# sensie.net
KiCad netlist of a schematic drawn in EAGLE
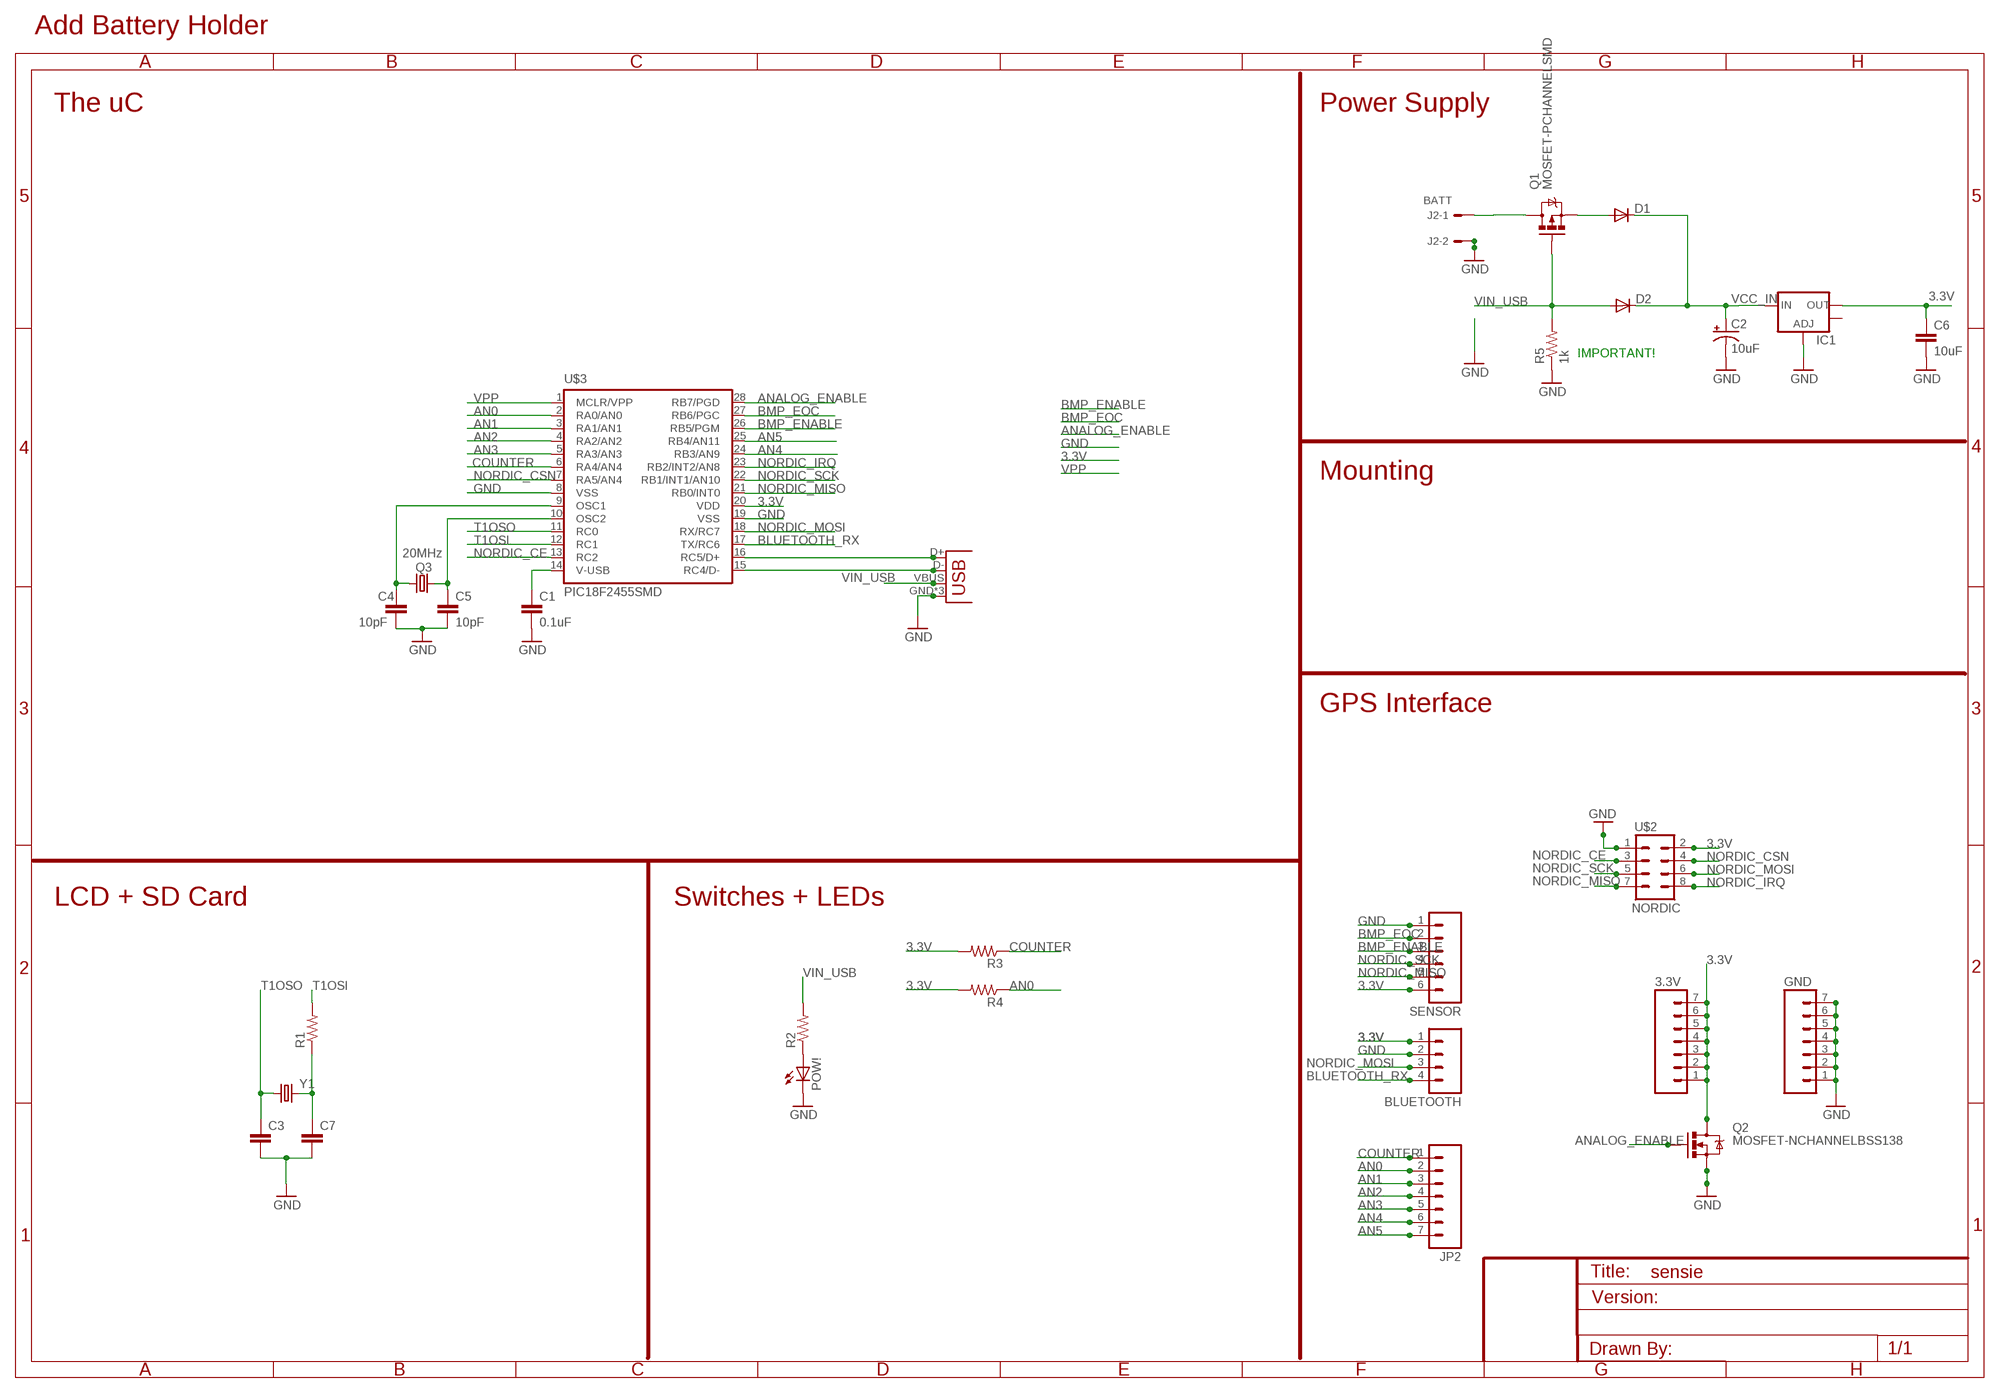
[diagram p0: schematic, sheet 1]

(export (version "E")
  (design (tool "Eeschema 10.0.6"))
  (components
    (comp (ref "3.3V")
      (value "M07")
      (footprint "eagle-import:1X07")
      (libsource (lib "eagle-import") (part "M07"))
    )
    (comp (ref "BLUETOOTH")
      (value "M04PTH")
      (footprint "eagle-import:1X04")
      (libsource (lib "eagle-import") (part "M04PTH"))
    )
    (comp (ref "C1")
      (value "0.1uF")
      (footprint "eagle-import:0805")
      (libsource (lib "eagle-import") (part "CAP0805"))
    )
    (comp (ref "C2")
      (value "10uF")
      (footprint "eagle-import:EIA3528")
      (libsource (lib "eagle-import") (part "CAP_POL3528"))
    )
    (comp (ref "C3")
      (value "CAP0603-CAP")
      (footprint "eagle-import:0603-CAP")
      (libsource (lib "eagle-import") (part "SparkFun-Passives_CAP0603-CAP"))
    )
    (comp (ref "C4")
      (value "10pF")
      (footprint "eagle-import:0805")
      (libsource (lib "eagle-import") (part "CAP0805"))
    )
    (comp (ref "C5")
      (value "10pF")
      (footprint "eagle-import:0805")
      (libsource (lib "eagle-import") (part "CAP0805"))
    )
    (comp (ref "C6")
      (value "10uF")
      (footprint "eagle-import:GRM43D")
      (libsource (lib "eagle-import") (part "CAPSMD"))
    )
    (comp (ref "C7")
      (value "CAP0603-CAP")
      (footprint "eagle-import:0603-CAP")
      (libsource (lib "eagle-import") (part "SparkFun-Passives_CAP0603-CAP"))
    )
    (comp (ref "D1")
      (value "DIODESOD")
      (footprint "eagle-import:SOD-323")
      (libsource (lib "eagle-import") (part "DIODESOD"))
    )
    (comp (ref "D2")
      (value "DIODESOD")
      (footprint "eagle-import:SOD-323")
      (libsource (lib "eagle-import") (part "DIODESOD"))
    )
    (comp (ref "GND")
      (value "M07")
      (footprint "eagle-import:1X07")
      (libsource (lib "eagle-import") (part "M07"))
    )
    (comp (ref "IC1")
      (value "V_REG_LM1117SOT223")
      (footprint "eagle-import:SOT223")
      (libsource (lib "eagle-import") (part "V_REG_LM1117SOT223"))
    )
    (comp (ref "J2")
      (value "BATT")
      (footprint "eagle-import:B2B-PH-K-S")
      (libsource (lib "eagle-import") (part "JST-PH-2-BS"))
    )
    (comp (ref "JP2")
      (value "M07")
      (footprint "eagle-import:1X07")
      (libsource (lib "eagle-import") (part "M07"))
    )
    (comp (ref "JP3")
      (value "USB-MICROB")
      (footprint "eagle-import:USB-MICROB")
      (libsource (lib "eagle-import") (part "USB-MICROB"))
    )
    (comp (ref "POW!")
      (value "LED0603")
      (footprint "eagle-import:LED-0603")
      (libsource (lib "eagle-import") (part "LED0603"))
    )
    (comp (ref "Q1")
      (value "MOSFET-PCHANNELSMD")
      (footprint "eagle-import:SOT23-3")
      (libsource (lib "eagle-import") (part "MOSFET-PCHANNELSMD"))
    )
    (comp (ref "Q2")
      (value "MOSFET-NCHANNELBSS138")
      (footprint "eagle-import:SOT23")
      (libsource (lib "eagle-import") (part "MOSFET-NCHANNELBSS138"))
    )
    (comp (ref "Q3")
      (value "20MHz")
      (footprint "eagle-import:HC49UP")
      (libsource (lib "eagle-import") (part "CRYSTALSMD"))
    )
    (comp (ref "R1")
      (value "RESISTOR0603-RES")
      (footprint "eagle-import:0603-RES")
      (libsource (lib "eagle-import") (part "SparkFun-Passives_RESISTOR0603-RES"))
    )
    (comp (ref "R2")
      (value "RESISTOR0603-RES")
      (footprint "eagle-import:0603-RES")
      (libsource (lib "eagle-import") (part "SparkFun-Passives_RESISTOR0603-RES"))
    )
    (comp (ref "R3")
      (value "RESISTOR0603-RES")
      (footprint "eagle-import:0603-RES")
      (libsource (lib "eagle-import") (part "SparkFun-Passives_RESISTOR0603-RES"))
    )
    (comp (ref "R4")
      (value "RESISTOR0603-RES")
      (footprint "eagle-import:0603-RES")
      (libsource (lib "eagle-import") (part "SparkFun-Passives_RESISTOR0603-RES"))
    )
    (comp (ref "R5")
      (value "1k")
      (footprint "eagle-import:0805")
      (libsource (lib "eagle-import") (part "RESISTOR"))
    )
    (comp (ref "SENSOR")
      (value "M06SIP")
      (footprint "eagle-import:1X06")
      (libsource (lib "eagle-import") (part "M06SIP"))
    )
    (comp (ref "U$2")
      (value "NORDIC")
      (footprint "eagle-import:2X4")
      (libsource (lib "eagle-import") (part "M04X2"))
    )
    (comp (ref "U$3")
      (value "PIC18F2455SMD")
      (footprint "eagle-import:SO-28W")
      (libsource (lib "eagle-import") (part "PIC18F2455SMD"))
    )
    (comp (ref "Y1")
      (value "CRYSTAL32-SMD")
      (footprint "eagle-import:CRYSTAL-32KHZ-SMD")
      (libsource (lib "eagle-import") (part "SparkFun-FreqCtrl_CRYSTAL32-SMD"))
    )
  )
  (nets
    (net (code "1") (name "/3.3V") (class "Default")
      (node (ref "3.3V") (pin "1") (pinfunction "1_1") (pintype "passive"))
      (node (ref "3.3V") (pin "2") (pinfunction "2_2") (pintype "passive"))
      (node (ref "3.3V") (pin "3") (pinfunction "3_3") (pintype "passive"))
      (node (ref "3.3V") (pin "4") (pinfunction "4_4") (pintype "passive"))
      (node (ref "3.3V") (pin "5") (pinfunction "5_5") (pintype "passive"))
      (node (ref "3.3V") (pin "6") (pinfunction "6_6") (pintype "passive"))
      (node (ref "3.3V") (pin "7") (pinfunction "7_7") (pintype "passive"))
      (node (ref "BLUETOOTH") (pin "1") (pinfunction "1_1") (pintype "passive"))
      (node (ref "C6") (pin "A") (pinfunction "1_A") (pintype "passive"))
      (node (ref "IC1") (pin "2") (pinfunction "OUT_2") (pintype "output"))
      (node (ref "Q2") (pin "3") (pinfunction "D_3") (pintype "passive"))
      (node (ref "R3") (pin "2") (pinfunction "2_2") (pintype "passive"))
      (node (ref "R4") (pin "2") (pinfunction "2_2") (pintype "passive"))
      (node (ref "SENSOR") (pin "6") (pinfunction "6_6") (pintype "passive"))
      (node (ref "U$2") (pin "2") (pinfunction "2_2") (pintype "passive"))
      (node (ref "U$3") (pin "20") (pinfunction "VDD_20") (pintype "power_in"))
    )
    (net (code "2") (name "/AN0") (class "Default")
      (node (ref "JP2") (pin "2") (pinfunction "2_2") (pintype "passive"))
      (node (ref "R4") (pin "1") (pinfunction "1_1") (pintype "passive"))
      (node (ref "U$3") (pin "2") (pinfunction "RA0/AN0_2") (pintype "bidirectional"))
    )
    (net (code "3") (name "/AN1") (class "Default")
      (node (ref "JP2") (pin "3") (pinfunction "3_3") (pintype "passive"))
      (node (ref "U$3") (pin "3") (pinfunction "RA1/AN1_3") (pintype "bidirectional"))
    )
    (net (code "4") (name "/AN2") (class "Default")
      (node (ref "JP2") (pin "4") (pinfunction "4_4") (pintype "passive"))
      (node (ref "U$3") (pin "4") (pinfunction "RA2/AN2_4") (pintype "bidirectional"))
    )
    (net (code "5") (name "/AN3") (class "Default")
      (node (ref "JP2") (pin "5") (pinfunction "5_5") (pintype "passive"))
      (node (ref "U$3") (pin "5") (pinfunction "RA3/AN3_5") (pintype "bidirectional"))
    )
    (net (code "6") (name "/AN4") (class "Default")
      (node (ref "JP2") (pin "6") (pinfunction "6_6") (pintype "passive"))
      (node (ref "U$3") (pin "24") (pinfunction "RB3/AN9_24") (pintype "bidirectional"))
    )
    (net (code "7") (name "/AN5") (class "Default")
      (node (ref "JP2") (pin "7") (pinfunction "7_7") (pintype "passive"))
      (node (ref "U$3") (pin "25") (pinfunction "RB4/AN11_25") (pintype "bidirectional"))
    )
    (net (code "8") (name "/ANALOG_ENABLE") (class "Default")
      (node (ref "Q2") (pin "1") (pinfunction "G_1") (pintype "passive"))
      (node (ref "U$3") (pin "28") (pinfunction "RB7/PGD_28") (pintype "bidirectional"))
    )
    (net (code "9") (name "/BLUETOOTH_RX") (class "Default")
      (node (ref "BLUETOOTH") (pin "4") (pinfunction "4_4") (pintype "passive"))
      (node (ref "U$3") (pin "17") (pinfunction "TX/RC6_17") (pintype "bidirectional"))
    )
    (net (code "10") (name "/BMP_ENABLE") (class "Default")
      (node (ref "SENSOR") (pin "3") (pinfunction "3_3") (pintype "passive"))
      (node (ref "U$3") (pin "26") (pinfunction "RB5/PGM_26") (pintype "bidirectional"))
    )
    (net (code "11") (name "/BMP_EOC") (class "Default")
      (node (ref "SENSOR") (pin "2") (pinfunction "2_2") (pintype "passive"))
      (node (ref "U$3") (pin "27") (pinfunction "RB6/PGC_27") (pintype "bidirectional"))
    )
    (net (code "12") (name "/COUNTER") (class "Default")
      (node (ref "JP2") (pin "1") (pinfunction "1_1") (pintype "passive"))
      (node (ref "R3") (pin "1") (pinfunction "1_1") (pintype "passive"))
      (node (ref "U$3") (pin "6") (pinfunction "RA4/AN4_6") (pintype "bidirectional"))
    )
    (net (code "13") (name "/NORDIC_CE") (class "Default")
      (node (ref "U$2") (pin "3") (pinfunction "3_3") (pintype "passive"))
      (node (ref "U$3") (pin "13") (pinfunction "RC2_13") (pintype "bidirectional"))
    )
    (net (code "14") (name "/NORDIC_CSN") (class "Default")
      (node (ref "U$2") (pin "4") (pinfunction "4_4") (pintype "passive"))
      (node (ref "U$3") (pin "7") (pinfunction "RA5/AN4_7") (pintype "bidirectional"))
    )
    (net (code "15") (name "/NORDIC_IRQ") (class "Default")
      (node (ref "U$2") (pin "8") (pinfunction "8_8") (pintype "passive"))
      (node (ref "U$3") (pin "23") (pinfunction "RB2/INT2/AN8_23") (pintype "bidirectional"))
    )
    (net (code "16") (name "/NORDIC_MISO") (class "Default")
      (node (ref "SENSOR") (pin "5") (pinfunction "5_5") (pintype "passive"))
      (node (ref "U$2") (pin "7") (pinfunction "7_7") (pintype "passive"))
      (node (ref "U$3") (pin "21") (pinfunction "RB0/INT0_21") (pintype "bidirectional"))
    )
    (net (code "17") (name "/NORDIC_MOSI") (class "Default")
      (node (ref "BLUETOOTH") (pin "3") (pinfunction "3_3") (pintype "passive"))
      (node (ref "U$2") (pin "6") (pinfunction "6_6") (pintype "passive"))
      (node (ref "U$3") (pin "18") (pinfunction "RX/RC7_18") (pintype "input"))
    )
    (net (code "18") (name "/NORDIC_SCK") (class "Default")
      (node (ref "SENSOR") (pin "4") (pinfunction "4_4") (pintype "passive"))
      (node (ref "U$2") (pin "5") (pinfunction "5_5") (pintype "passive"))
      (node (ref "U$3") (pin "22") (pinfunction "RB1/INT1/AN10_22") (pintype "bidirectional"))
    )
    (net (code "19") (name "/T1OSI") (class "Default")
      (node (ref "R1") (pin "2") (pinfunction "2_2") (pintype "passive"))
      (node (ref "U$3") (pin "12") (pinfunction "RC1_12") (pintype "bidirectional"))
    )
    (net (code "20") (name "/T1OSO") (class "Default")
      (node (ref "C3") (pin "1") (pinfunction "1_1") (pintype "passive"))
      (node (ref "U$3") (pin "11") (pinfunction "RC0_11") (pintype "bidirectional"))
      (node (ref "Y1") (pin "X1") (pinfunction "1_X1") (pintype "passive"))
    )
    (net (code "21") (name "/VCC_IN") (class "Default")
      (node (ref "C2") (pin "A") (pinfunction "+_A") (pintype "passive"))
      (node (ref "D1") (pin "1") (pinfunction "C_1") (pintype "passive"))
      (node (ref "D2") (pin "1") (pinfunction "C_1") (pintype "passive"))
      (node (ref "IC1") (pin "3") (pinfunction "IN_3") (pintype "input"))
    )
    (net (code "22") (name "/VIN_USB") (class "Default")
      (node (ref "D2") (pin "2") (pinfunction "A_2") (pintype "passive"))
      (node (ref "JP3") (pin "VBUS") (pinfunction "VBUS_VBUS") (pintype "bidirectional"))
      (node (ref "Q1") (pin "1") (pinfunction "G_1") (pintype "passive"))
      (node (ref "R2") (pin "2") (pinfunction "2_2") (pintype "passive"))
      (node (ref "R5") (pin "2") (pinfunction "2_2") (pintype "passive"))
    )
    (net (code "23") (name "/VPP") (class "Default")
      (node (ref "U$3") (pin "1") (pinfunction "MCLR/VPP_1") (pintype "bidirectional"))
    )
    (net (code "24") (name "GND") (class "Default")
      (node (ref "BLUETOOTH") (pin "2") (pinfunction "2_2") (pintype "passive"))
      (node (ref "C1") (pin "2") (pinfunction "2_2") (pintype "passive"))
      (node (ref "C2") (pin "C") (pinfunction "-_C") (pintype "passive"))
      (node (ref "C3") (pin "2") (pinfunction "2_2") (pintype "passive"))
      (node (ref "C4") (pin "2") (pinfunction "2_2") (pintype "passive"))
      (node (ref "C5") (pin "2") (pinfunction "2_2") (pintype "passive"))
      (node (ref "C6") (pin "C") (pinfunction "2_C") (pintype "passive"))
      (node (ref "C7") (pin "2") (pinfunction "2_2") (pintype "passive"))
      (node (ref "GND") (pin "1") (pinfunction "1_1") (pintype "passive"))
      (node (ref "GND") (pin "2") (pinfunction "2_2") (pintype "passive"))
      (node (ref "GND") (pin "3") (pinfunction "3_3") (pintype "passive"))
      (node (ref "GND") (pin "4") (pinfunction "4_4") (pintype "passive"))
      (node (ref "GND") (pin "5") (pinfunction "5_5") (pintype "passive"))
      (node (ref "GND") (pin "6") (pinfunction "6_6") (pintype "passive"))
      (node (ref "GND") (pin "7") (pinfunction "7_7") (pintype "passive"))
      (node (ref "IC1") (pin "1") (pinfunction "ADJ_1") (pintype "input"))
      (node (ref "J2") (pin "2") (pinfunction "S_2") (pintype "passive"))
      (node (ref "JP3") (pin "GND") (pinfunction "GND_GND") (pintype "bidirectional"))
      (node (ref "JP3") (pin "P$3") (pinfunction "GND_P$3") (pintype "bidirectional"))
      (node (ref "JP3") (pin "P$4") (pinfunction "GND_P$4") (pintype "bidirectional"))
      (node (ref "POW!") (pin "C") (pinfunction "C_C") (pintype "passive"))
      (node (ref "Q2") (pin "2") (pinfunction "S_2") (pintype "passive"))
      (node (ref "R5") (pin "1") (pinfunction "1_1") (pintype "passive"))
      (node (ref "SENSOR") (pin "1") (pinfunction "1_1") (pintype "passive"))
      (node (ref "U$2") (pin "1") (pinfunction "1_1") (pintype "passive"))
      (node (ref "U$3") (pin "19") (pinfunction "VSS_19") (pintype "power_in"))
      (node (ref "U$3") (pin "8") (pinfunction "VSS_8") (pintype "power_in"))
    )
    (net (code "25") (name "Net-(D1-A)") (class "Default")
      (node (ref "D1") (pin "2") (pinfunction "A_2") (pintype "passive"))
      (node (ref "Q1") (pin "2") (pinfunction "S_2") (pintype "passive"))
    )
    (net (code "26") (name "Net-(J2A-S)") (class "Default")
      (node (ref "J2") (pin "1") (pinfunction "S_1") (pintype "passive"))
      (node (ref "Q1") (pin "3") (pinfunction "D_3") (pintype "passive"))
    )
    (net (code "27") (name "Net-(POW!-PadA)") (class "Default")
      (node (ref "POW!") (pin "A") (pinfunction "A_A") (pintype "passive"))
      (node (ref "R2") (pin "1") (pinfunction "1_1") (pintype "passive"))
    )
    (net (code "28") (name "Net-(U$3-OSC1)") (class "Default")
      (node (ref "C4") (pin "1") (pinfunction "1_1") (pintype "passive"))
      (node (ref "Q3") (pin "1") (pinfunction "1_1") (pintype "passive"))
      (node (ref "U$3") (pin "9") (pinfunction "OSC1_9") (pintype "bidirectional"))
    )
    (net (code "29") (name "Net-(U$3-OSC2)") (class "Default")
      (node (ref "C5") (pin "1") (pinfunction "1_1") (pintype "passive"))
      (node (ref "Q3") (pin "2") (pinfunction "2_2") (pintype "passive"))
      (node (ref "U$3") (pin "10") (pinfunction "OSC2_10") (pintype "bidirectional"))
    )
    (net (code "30") (name "Net-(U$3-RC4{slash}D-)") (class "Default")
      (node (ref "JP3") (pin "D-") (pinfunction "D-_D-") (pintype "bidirectional"))
      (node (ref "U$3") (pin "15") (pinfunction "RC4/D-_15") (pintype "bidirectional"))
    )
    (net (code "31") (name "Net-(U$3-RC5{slash}D+)") (class "Default")
      (node (ref "JP3") (pin "D+") (pinfunction "D+_D+") (pintype "bidirectional"))
      (node (ref "U$3") (pin "16") (pinfunction "RC5/D+_16") (pintype "bidirectional"))
    )
    (net (code "32") (name "Net-(U$3-V-USB)") (class "Default")
      (node (ref "C1") (pin "1") (pinfunction "1_1") (pintype "passive"))
      (node (ref "U$3") (pin "14") (pinfunction "V-USB_14") (pintype "bidirectional"))
    )
    (net (code "33") (name "Net-(Y1-2)") (class "Default")
      (node (ref "C7") (pin "1") (pinfunction "1_1") (pintype "passive"))
      (node (ref "R1") (pin "1") (pinfunction "1_1") (pintype "passive"))
      (node (ref "Y1") (pin "X2") (pinfunction "2_X2") (pintype "passive"))
    )
    (net (code "34") (name "unconnected-(IC1-OUT-Pad4)") (class "Default")
      (node (ref "IC1") (pin "4") (pinfunction "OUT_4") (pintype "output"))
    )
  )
)
